# RP2350B_DEV_Template.net
KiCad netlist of a schematic drawn in EAGLE
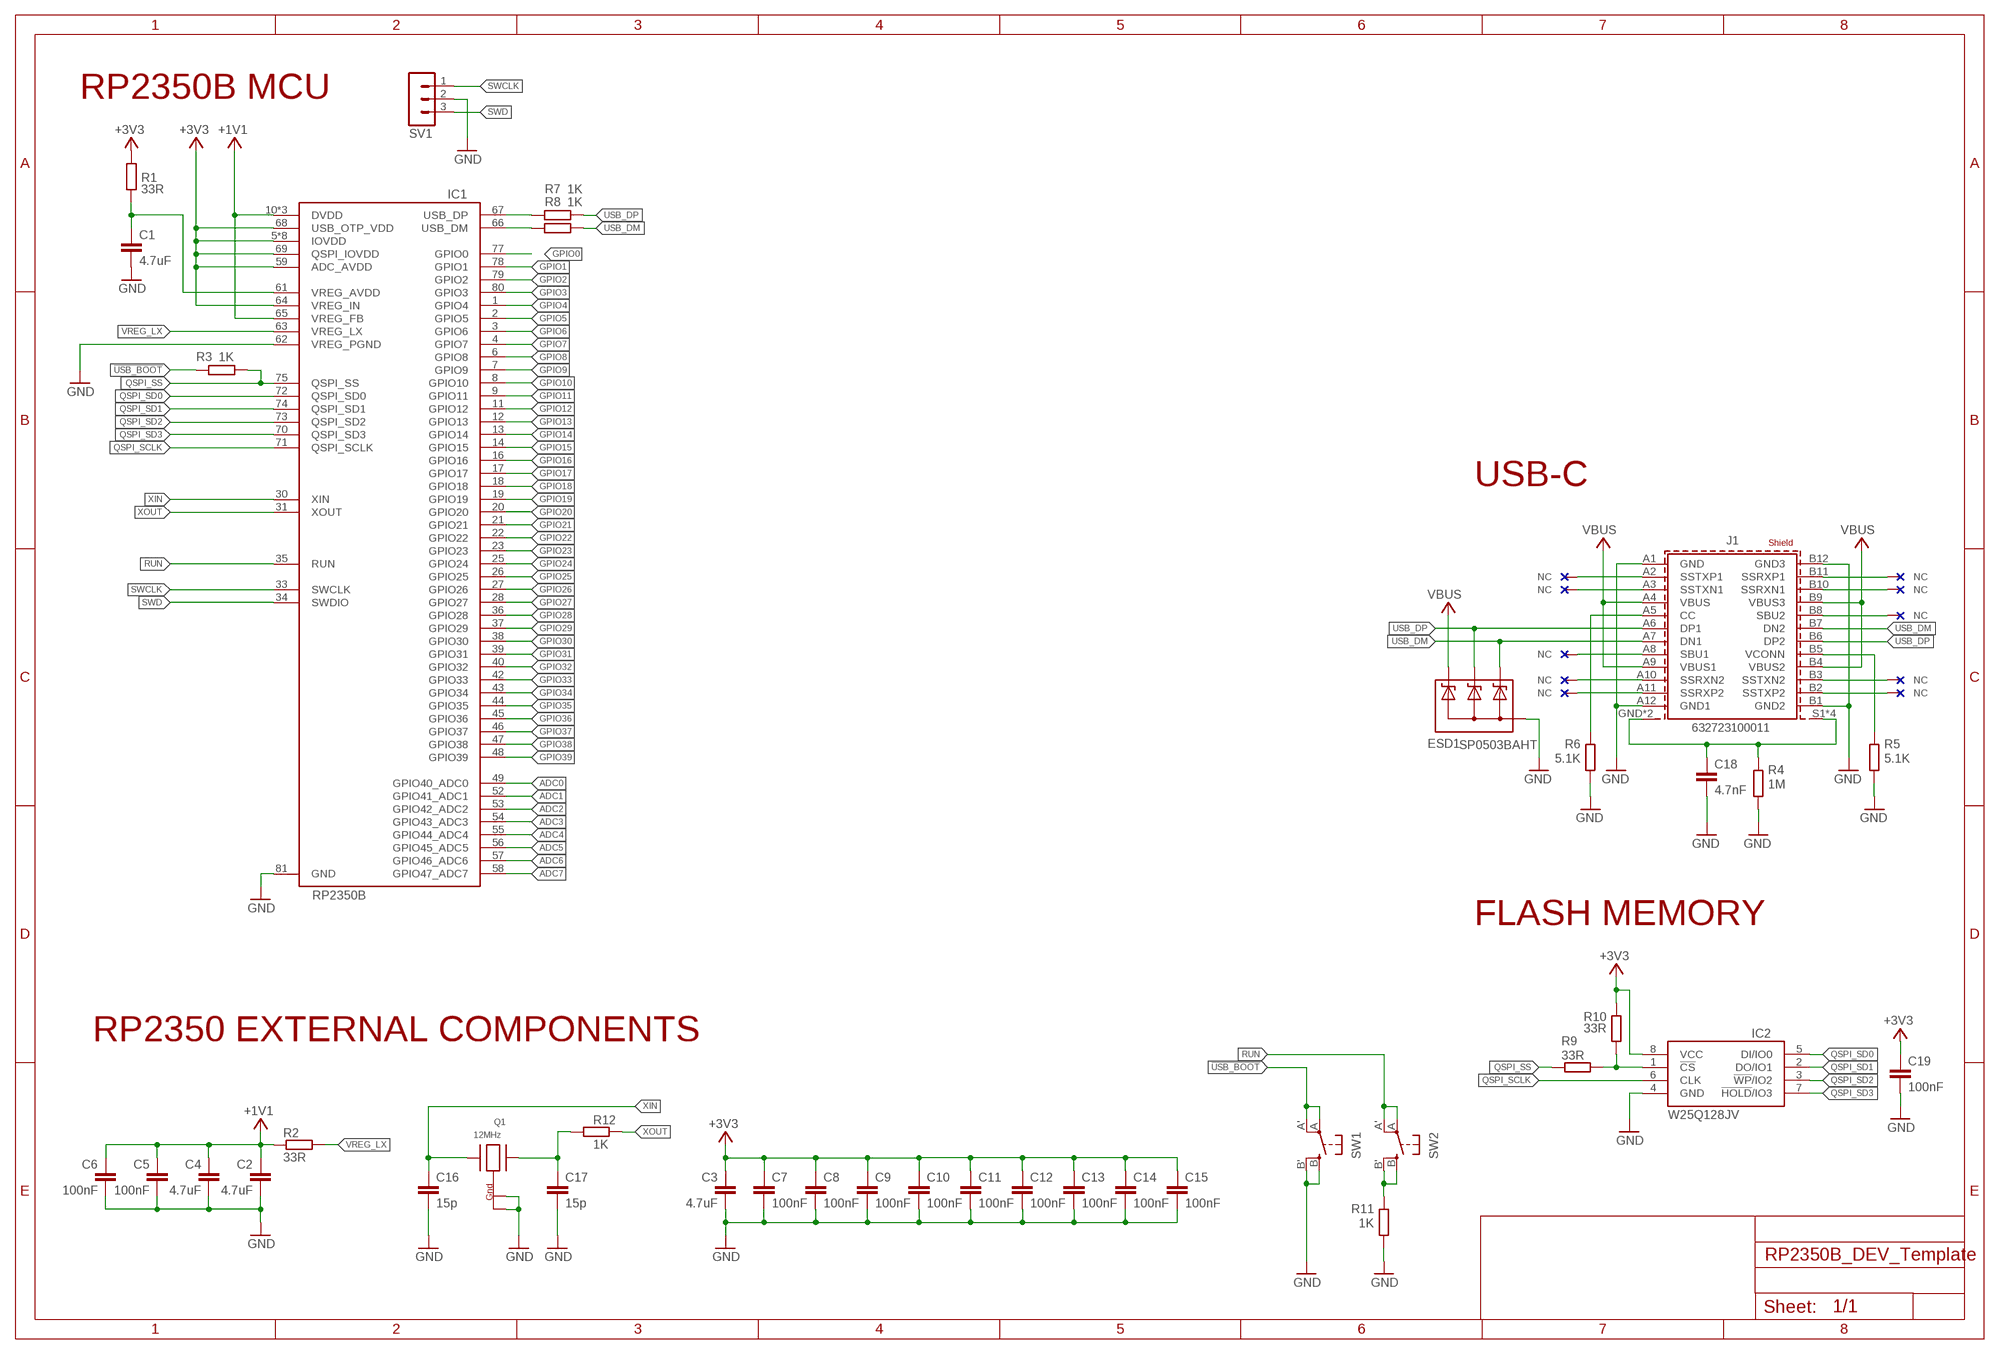
[diagram p0: schematic, sheet 1]

(export (version "E")
  (design (tool "Eeschema 10.0.6"))
  (components
    (comp (ref "C1")
      (value "4.7uF")
      (footprint "eagle-import:C0402K")
      (libsource (lib "eagle-import") (part "C-EUC0402K"))
    )
    (comp (ref "C2")
      (value "4.7uF")
      (footprint "eagle-import:C0402K")
      (libsource (lib "eagle-import") (part "C-EUC0402K"))
    )
    (comp (ref "C3")
      (value "4.7uF")
      (footprint "eagle-import:C0402K")
      (libsource (lib "eagle-import") (part "C-EUC0402K"))
    )
    (comp (ref "C4")
      (value "4.7uF")
      (footprint "eagle-import:C0402K")
      (libsource (lib "eagle-import") (part "C-EUC0402K"))
    )
    (comp (ref "C5")
      (value "100nF")
      (footprint "eagle-import:C0402K")
      (libsource (lib "eagle-import") (part "C-EUC0402K"))
    )
    (comp (ref "C6")
      (value "100nF")
      (footprint "eagle-import:C0402K")
      (libsource (lib "eagle-import") (part "C-EUC0402K"))
    )
    (comp (ref "C7")
      (value "100nF")
      (footprint "eagle-import:C0402K")
      (libsource (lib "eagle-import") (part "C-EUC0402K"))
    )
    (comp (ref "C8")
      (value "100nF")
      (footprint "eagle-import:C0402K")
      (libsource (lib "eagle-import") (part "C-EUC0402K"))
    )
    (comp (ref "C9")
      (value "100nF")
      (footprint "eagle-import:C0402K")
      (libsource (lib "eagle-import") (part "C-EUC0402K"))
    )
    (comp (ref "C10")
      (value "100nF")
      (footprint "eagle-import:C0402K")
      (libsource (lib "eagle-import") (part "C-EUC0402K"))
    )
    (comp (ref "C11")
      (value "100nF")
      (footprint "eagle-import:C0402K")
      (libsource (lib "eagle-import") (part "C-EUC0402K"))
    )
    (comp (ref "C12")
      (value "100nF")
      (footprint "eagle-import:C0402K")
      (libsource (lib "eagle-import") (part "C-EUC0402K"))
    )
    (comp (ref "C13")
      (value "100nF")
      (footprint "eagle-import:C0402K")
      (libsource (lib "eagle-import") (part "C-EUC0402K"))
    )
    (comp (ref "C14")
      (value "100nF")
      (footprint "eagle-import:C0402K")
      (libsource (lib "eagle-import") (part "C-EUC0402K"))
    )
    (comp (ref "C15")
      (value "100nF")
      (footprint "eagle-import:C0402K")
      (libsource (lib "eagle-import") (part "C-EUC0402K"))
    )
    (comp (ref "C16")
      (value "15p")
      (footprint "eagle-import:C0402K")
      (libsource (lib "eagle-import") (part "C-EUC0402K"))
    )
    (comp (ref "C17")
      (value "15p")
      (footprint "eagle-import:C0402K")
      (libsource (lib "eagle-import") (part "C-EUC0402K"))
    )
    (comp (ref "C18")
      (value "4.7nF")
      (footprint "eagle-import:C0402K")
      (libsource (lib "eagle-import") (part "C-EUC0402K"))
    )
    (comp (ref "C19")
      (value "100nF")
      (footprint "eagle-import:C0402K")
      (libsource (lib "eagle-import") (part "C-EUC0402K"))
    )
    (comp (ref "ESD1")
      (value "SP0503BAHT")
      (footprint "eagle-import:SOT143")
      (libsource (lib "eagle-import") (part "SP0503BAHT"))
    )
    (comp (ref "IC1")
      (value "RP2350BB")
      (footprint "eagle-import:QFN40P1000X1000X85-81T340N")
      (libsource (lib "eagle-import") (part "RP2350BB"))
    )
    (comp (ref "IC2")
      (value "W25Q128JVP")
      (footprint "eagle-import:SON127P600X500X75-8N")
      (libsource (lib "eagle-import") (part "W25Q128JVP"))
    )
    (comp (ref "J1")
      (value "632723100011")
      (footprint "eagle-import:632723100011")
      (libsource (lib "eagle-import") (part "632723100011"))
    )
    (comp (ref "Q1")
      (value "12MHz")
      (footprint "eagle-import:NX3225")
      (libsource (lib "eagle-import") (part "XTAL-4-3225"))
    )
    (comp (ref "R1")
      (value "33R")
      (footprint "eagle-import:R0402")
      (libsource (lib "eagle-import") (part "R-EU_R0402"))
    )
    (comp (ref "R2")
      (value "33R")
      (footprint "eagle-import:R0402")
      (libsource (lib "eagle-import") (part "R-EU_R0402"))
    )
    (comp (ref "R3")
      (value "1K")
      (footprint "eagle-import:R0402")
      (libsource (lib "eagle-import") (part "R-EU_R0402"))
    )
    (comp (ref "R4")
      (value "1M")
      (footprint "eagle-import:R0402")
      (libsource (lib "eagle-import") (part "R-EU_R0402"))
    )
    (comp (ref "R5")
      (value "5.1K")
      (footprint "eagle-import:R0402")
      (libsource (lib "eagle-import") (part "R-EU_R0402"))
    )
    (comp (ref "R6")
      (value "5.1K")
      (footprint "eagle-import:R0402")
      (libsource (lib "eagle-import") (part "R-EU_R0402"))
    )
    (comp (ref "R7")
      (value "1K")
      (footprint "eagle-import:R0402")
      (libsource (lib "eagle-import") (part "R-EU_R0402"))
    )
    (comp (ref "R8")
      (value "1K")
      (footprint "eagle-import:R0402")
      (libsource (lib "eagle-import") (part "R-EU_R0402"))
    )
    (comp (ref "R9")
      (value "33R")
      (footprint "eagle-import:R0402")
      (libsource (lib "eagle-import") (part "R-EU_R0402"))
    )
    (comp (ref "R10")
      (value "33R")
      (footprint "eagle-import:R0402")
      (libsource (lib "eagle-import") (part "R-EU_R0402"))
    )
    (comp (ref "R11")
      (value "1K")
      (footprint "eagle-import:R0402")
      (libsource (lib "eagle-import") (part "R-EU_R0402"))
    )
    (comp (ref "R12")
      (value "1K")
      (footprint "eagle-import:R0402")
      (libsource (lib "eagle-import") (part "R-EU_R0402"))
    )
    (comp (ref "SV1")
      (value "MA03-1")
      (footprint "eagle-import:MA03-1")
      (libsource (lib "eagle-import") (part "MA03-1"))
    )
    (comp (ref "SW1")
      (value "SPST_TACT-EVQQ2")
      (footprint "eagle-import:EVQ-Q2")
      (libsource (lib "eagle-import") (part "SPST_TACT-EVQQ2"))
    )
    (comp (ref "SW2")
      (value "SPST_TACT-EVQQ2")
      (footprint "eagle-import:EVQ-Q2")
      (libsource (lib "eagle-import") (part "SPST_TACT-EVQQ2"))
    )
  )
  (nets
    (net (code "1") (name "+1V1") (class "Default")
      (node (ref "C2") (pin "1") (pinfunction "1_1") (pintype "passive"))
      (node (ref "C4") (pin "1") (pinfunction "1_1") (pintype "passive"))
      (node (ref "C5") (pin "1") (pinfunction "1_1") (pintype "passive"))
      (node (ref "C6") (pin "1") (pinfunction "1_1") (pintype "passive"))
      (node (ref "IC1") (pin "10") (pinfunction "DVDD_10") (pintype "power_in"))
      (node (ref "IC1") (pin "32") (pinfunction "DVDD_32") (pintype "power_in"))
      (node (ref "IC1") (pin "51") (pinfunction "DVDD_51") (pintype "power_in"))
      (node (ref "IC1") (pin "65") (pinfunction "VREG_FB_65") (pintype "power_in"))
      (node (ref "R2") (pin "2") (pinfunction "2_2") (pintype "passive"))
    )
    (net (code "2") (name "+3V3") (class "Default")
      (node (ref "C10") (pin "1") (pinfunction "1_1") (pintype "passive"))
      (node (ref "C11") (pin "1") (pinfunction "1_1") (pintype "passive"))
      (node (ref "C12") (pin "1") (pinfunction "1_1") (pintype "passive"))
      (node (ref "C13") (pin "1") (pinfunction "1_1") (pintype "passive"))
      (node (ref "C14") (pin "1") (pinfunction "1_1") (pintype "passive"))
      (node (ref "C15") (pin "1") (pinfunction "1_1") (pintype "passive"))
      (node (ref "C19") (pin "1") (pinfunction "1_1") (pintype "passive"))
      (node (ref "C3") (pin "1") (pinfunction "1_1") (pintype "passive"))
      (node (ref "C7") (pin "1") (pinfunction "1_1") (pintype "passive"))
      (node (ref "C8") (pin "1") (pinfunction "1_1") (pintype "passive"))
      (node (ref "C9") (pin "1") (pinfunction "1_1") (pintype "passive"))
      (node (ref "IC1") (pin "15") (pinfunction "IOVDD_15") (pintype "power_in"))
      (node (ref "IC1") (pin "24") (pinfunction "IOVDD_24") (pintype "power_in"))
      (node (ref "IC1") (pin "29") (pinfunction "IOVDD_29") (pintype "power_in"))
      (node (ref "IC1") (pin "41") (pinfunction "IOVDD_41") (pintype "power_in"))
      (node (ref "IC1") (pin "5") (pinfunction "IOVDD_5") (pintype "power_in"))
      (node (ref "IC1") (pin "50") (pinfunction "IOVDD_50") (pintype "power_in"))
      (node (ref "IC1") (pin "59") (pinfunction "ADC_AVDD_59") (pintype "power_in"))
      (node (ref "IC1") (pin "60") (pinfunction "IOVDD_60") (pintype "power_in"))
      (node (ref "IC1") (pin "64") (pinfunction "VREG_IN_64") (pintype "power_in"))
      (node (ref "IC1") (pin "68") (pinfunction "USB_OTP_VDD_68") (pintype "bidirectional"))
      (node (ref "IC1") (pin "69") (pinfunction "QSPI_IOVDD_69") (pintype "power_in"))
      (node (ref "IC1") (pin "76") (pinfunction "IOVDD_76") (pintype "power_in"))
      (node (ref "IC2") (pin "8") (pinfunction "VCC_8") (pintype "power_in"))
      (node (ref "R1") (pin "1") (pinfunction "1_1") (pintype "passive"))
      (node (ref "R10") (pin "1") (pinfunction "1_1") (pintype "passive"))
    )
    (net (code "3") (name "/~{USB_BOOT}") (class "Default")
      (node (ref "R3") (pin "1") (pinfunction "1_1") (pintype "passive"))
      (node (ref "SW1") (pin "A") (pinfunction "P_A") (pintype "passive"))
      (node (ref "SW1") (pin "A'") (pinfunction "P1_A'") (pintype "passive"))
    )
    (net (code "4") (name "ADC0") (class "Default")
      (node (ref "IC1") (pin "49") (pinfunction "GPIO40_ADC0_49") (pintype "bidirectional"))
    )
    (net (code "5") (name "ADC1") (class "Default")
      (node (ref "IC1") (pin "52") (pinfunction "GPIO41_ADC1_52") (pintype "bidirectional"))
    )
    (net (code "6") (name "ADC2") (class "Default")
      (node (ref "IC1") (pin "53") (pinfunction "GPIO42_ADC2_53") (pintype "bidirectional"))
    )
    (net (code "7") (name "ADC3") (class "Default")
      (node (ref "IC1") (pin "54") (pinfunction "GPIO43_ADC3_54") (pintype "bidirectional"))
    )
    (net (code "8") (name "ADC4") (class "Default")
      (node (ref "IC1") (pin "55") (pinfunction "GPIO44_ADC4_55") (pintype "bidirectional"))
    )
    (net (code "9") (name "ADC5") (class "Default")
      (node (ref "IC1") (pin "56") (pinfunction "GPIO45_ADC5_56") (pintype "bidirectional"))
    )
    (net (code "10") (name "ADC6") (class "Default")
      (node (ref "IC1") (pin "57") (pinfunction "GPIO46_ADC6_57") (pintype "bidirectional"))
    )
    (net (code "11") (name "ADC7") (class "Default")
      (node (ref "IC1") (pin "58") (pinfunction "GPIO47_ADC7_58") (pintype "bidirectional"))
    )
    (net (code "12") (name "GND") (class "Default")
      (node (ref "C1") (pin "2") (pinfunction "2_2") (pintype "passive"))
      (node (ref "C10") (pin "2") (pinfunction "2_2") (pintype "passive"))
      (node (ref "C11") (pin "2") (pinfunction "2_2") (pintype "passive"))
      (node (ref "C12") (pin "2") (pinfunction "2_2") (pintype "passive"))
      (node (ref "C13") (pin "2") (pinfunction "2_2") (pintype "passive"))
      (node (ref "C14") (pin "2") (pinfunction "2_2") (pintype "passive"))
      (node (ref "C15") (pin "2") (pinfunction "2_2") (pintype "passive"))
      (node (ref "C16") (pin "2") (pinfunction "2_2") (pintype "passive"))
      (node (ref "C17") (pin "2") (pinfunction "2_2") (pintype "passive"))
      (node (ref "C18") (pin "2") (pinfunction "2_2") (pintype "passive"))
      (node (ref "C19") (pin "2") (pinfunction "2_2") (pintype "passive"))
      (node (ref "C2") (pin "2") (pinfunction "2_2") (pintype "passive"))
      (node (ref "C3") (pin "2") (pinfunction "2_2") (pintype "passive"))
      (node (ref "C4") (pin "2") (pinfunction "2_2") (pintype "passive"))
      (node (ref "C5") (pin "2") (pinfunction "2_2") (pintype "passive"))
      (node (ref "C6") (pin "2") (pinfunction "2_2") (pintype "passive"))
      (node (ref "C7") (pin "2") (pinfunction "2_2") (pintype "passive"))
      (node (ref "C8") (pin "2") (pinfunction "2_2") (pintype "passive"))
      (node (ref "C9") (pin "2") (pinfunction "2_2") (pintype "passive"))
      (node (ref "ESD1") (pin "1") (pinfunction "A_1") (pintype "bidirectional"))
      (node (ref "IC1") (pin "62") (pinfunction "VREG_PGND_62") (pintype "power_in"))
      (node (ref "IC1") (pin "81") (pinfunction "GND_81") (pintype "power_in"))
      (node (ref "IC2") (pin "4") (pinfunction "GND_4") (pintype "power_in"))
      (node (ref "J1") (pin "A1") (pinfunction "GND_A1") (pintype "passive"))
      (node (ref "J1") (pin "A12") (pinfunction "GND1_A12") (pintype "passive"))
      (node (ref "J1") (pin "B1") (pinfunction "GND2_B1") (pintype "passive"))
      (node (ref "J1") (pin "B12") (pinfunction "GND3_B12") (pintype "passive"))
      (node (ref "Q1") (pin "2") (pinfunction "G2_2") (pintype "power_in"))
      (node (ref "Q1") (pin "4") (pinfunction "G1_4") (pintype "power_in"))
      (node (ref "R11") (pin "1") (pinfunction "1_1") (pintype "passive"))
      (node (ref "R4") (pin "1") (pinfunction "1_1") (pintype "passive"))
      (node (ref "R5") (pin "1") (pinfunction "1_1") (pintype "passive"))
      (node (ref "R6") (pin "1") (pinfunction "1_1") (pintype "passive"))
      (node (ref "SV1") (pin "2") (pinfunction "2_2") (pintype "passive"))
      (node (ref "SW1") (pin "B") (pinfunction "S_B") (pintype "passive"))
      (node (ref "SW1") (pin "B'") (pinfunction "S1_B'") (pintype "passive"))
    )
    (net (code "13") (name "GPIO0") (class "Default")
      (node (ref "IC1") (pin "77") (pinfunction "GPIO0_77") (pintype "bidirectional"))
    )
    (net (code "14") (name "GPIO1") (class "Default")
      (node (ref "IC1") (pin "78") (pinfunction "GPIO1_78") (pintype "bidirectional"))
    )
    (net (code "15") (name "GPIO2") (class "Default")
      (node (ref "IC1") (pin "79") (pinfunction "GPIO2_79") (pintype "bidirectional"))
    )
    (net (code "16") (name "GPIO3") (class "Default")
      (node (ref "IC1") (pin "80") (pinfunction "GPIO3_80") (pintype "bidirectional"))
    )
    (net (code "17") (name "GPIO4") (class "Default")
      (node (ref "IC1") (pin "1") (pinfunction "GPIO4_1") (pintype "bidirectional"))
    )
    (net (code "18") (name "GPIO5") (class "Default")
      (node (ref "IC1") (pin "2") (pinfunction "GPIO5_2") (pintype "bidirectional"))
    )
    (net (code "19") (name "GPIO6") (class "Default")
      (node (ref "IC1") (pin "3") (pinfunction "GPIO6_3") (pintype "bidirectional"))
    )
    (net (code "20") (name "GPIO7") (class "Default")
      (node (ref "IC1") (pin "4") (pinfunction "GPIO7_4") (pintype "bidirectional"))
    )
    (net (code "21") (name "GPIO8") (class "Default")
      (node (ref "IC1") (pin "6") (pinfunction "GPIO8_6") (pintype "bidirectional"))
    )
    (net (code "22") (name "GPIO9") (class "Default")
      (node (ref "IC1") (pin "7") (pinfunction "GPIO9_7") (pintype "bidirectional"))
    )
    (net (code "23") (name "GPIO10") (class "Default")
      (node (ref "IC1") (pin "8") (pinfunction "GPIO10_8") (pintype "bidirectional"))
    )
    (net (code "24") (name "GPIO11") (class "Default")
      (node (ref "IC1") (pin "9") (pinfunction "GPIO11_9") (pintype "bidirectional"))
    )
    (net (code "25") (name "GPIO12") (class "Default")
      (node (ref "IC1") (pin "11") (pinfunction "GPIO12_11") (pintype "bidirectional"))
    )
    (net (code "26") (name "GPIO13") (class "Default")
      (node (ref "IC1") (pin "12") (pinfunction "GPIO13_12") (pintype "bidirectional"))
    )
    (net (code "27") (name "GPIO14") (class "Default")
      (node (ref "IC1") (pin "13") (pinfunction "GPIO14_13") (pintype "bidirectional"))
    )
    (net (code "28") (name "GPIO15") (class "Default")
      (node (ref "IC1") (pin "14") (pinfunction "GPIO15_14") (pintype "bidirectional"))
    )
    (net (code "29") (name "GPIO16") (class "Default")
      (node (ref "IC1") (pin "16") (pinfunction "GPIO16_16") (pintype "bidirectional"))
    )
    (net (code "30") (name "GPIO17") (class "Default")
      (node (ref "IC1") (pin "17") (pinfunction "GPIO17_17") (pintype "bidirectional"))
    )
    (net (code "31") (name "GPIO18") (class "Default")
      (node (ref "IC1") (pin "18") (pinfunction "GPIO18_18") (pintype "bidirectional"))
    )
    (net (code "32") (name "GPIO19") (class "Default")
      (node (ref "IC1") (pin "19") (pinfunction "GPIO19_19") (pintype "bidirectional"))
    )
    (net (code "33") (name "GPIO20") (class "Default")
      (node (ref "IC1") (pin "20") (pinfunction "GPIO20_20") (pintype "bidirectional"))
    )
    (net (code "34") (name "GPIO21") (class "Default")
      (node (ref "IC1") (pin "21") (pinfunction "GPIO21_21") (pintype "bidirectional"))
    )
    (net (code "35") (name "GPIO22") (class "Default")
      (node (ref "IC1") (pin "22") (pinfunction "GPIO22_22") (pintype "bidirectional"))
    )
    (net (code "36") (name "GPIO23") (class "Default")
      (node (ref "IC1") (pin "23") (pinfunction "GPIO23_23") (pintype "bidirectional"))
    )
    (net (code "37") (name "GPIO24") (class "Default")
      (node (ref "IC1") (pin "25") (pinfunction "GPIO24_25") (pintype "bidirectional"))
    )
    (net (code "38") (name "GPIO25") (class "Default")
      (node (ref "IC1") (pin "26") (pinfunction "GPIO25_26") (pintype "bidirectional"))
    )
    (net (code "39") (name "GPIO26") (class "Default")
      (node (ref "IC1") (pin "27") (pinfunction "GPIO26_27") (pintype "bidirectional"))
    )
    (net (code "40") (name "GPIO27") (class "Default")
      (node (ref "IC1") (pin "28") (pinfunction "GPIO27_28") (pintype "bidirectional"))
    )
    (net (code "41") (name "GPIO28") (class "Default")
      (node (ref "IC1") (pin "36") (pinfunction "GPIO28_36") (pintype "bidirectional"))
    )
    (net (code "42") (name "GPIO29") (class "Default")
      (node (ref "IC1") (pin "37") (pinfunction "GPIO29_37") (pintype "bidirectional"))
    )
    (net (code "43") (name "GPIO30") (class "Default")
      (node (ref "IC1") (pin "38") (pinfunction "GPIO30_38") (pintype "bidirectional"))
    )
    (net (code "44") (name "GPIO31") (class "Default")
      (node (ref "IC1") (pin "39") (pinfunction "GPIO31_39") (pintype "bidirectional"))
    )
    (net (code "45") (name "GPIO32") (class "Default")
      (node (ref "IC1") (pin "40") (pinfunction "GPIO32_40") (pintype "bidirectional"))
    )
    (net (code "46") (name "GPIO33") (class "Default")
      (node (ref "IC1") (pin "42") (pinfunction "GPIO33_42") (pintype "bidirectional"))
    )
    (net (code "47") (name "GPIO34") (class "Default")
      (node (ref "IC1") (pin "43") (pinfunction "GPIO34_43") (pintype "bidirectional"))
    )
    (net (code "48") (name "GPIO35") (class "Default")
      (node (ref "IC1") (pin "44") (pinfunction "GPIO35_44") (pintype "bidirectional"))
    )
    (net (code "49") (name "GPIO36") (class "Default")
      (node (ref "IC1") (pin "45") (pinfunction "GPIO36_45") (pintype "bidirectional"))
    )
    (net (code "50") (name "GPIO37") (class "Default")
      (node (ref "IC1") (pin "46") (pinfunction "GPIO37_46") (pintype "bidirectional"))
    )
    (net (code "51") (name "GPIO38") (class "Default")
      (node (ref "IC1") (pin "47") (pinfunction "GPIO38_47") (pintype "bidirectional"))
    )
    (net (code "52") (name "GPIO39") (class "Default")
      (node (ref "IC1") (pin "48") (pinfunction "GPIO39_48") (pintype "bidirectional"))
    )
    (net (code "53") (name "Net-(C18-Pad1)") (class "Default")
      (node (ref "C18") (pin "1") (pinfunction "1_1") (pintype "passive"))
      (node (ref "J1") (pin "GND") (pinfunction "SHIELD_GND") (pintype "passive"))
      (node (ref "J1") (pin "GND1") (pinfunction "SHIELD_GND1") (pintype "passive"))
      (node (ref "J1") (pin "S1") (pinfunction "SHIELD1_S1") (pintype "passive"))
      (node (ref "J1") (pin "S2") (pinfunction "SHIELD1_S2") (pintype "passive"))
      (node (ref "J1") (pin "S3") (pinfunction "SHIELD1_S3") (pintype "passive"))
      (node (ref "J1") (pin "S4") (pinfunction "SHIELD1_S4") (pintype "passive"))
      (node (ref "R4") (pin "2") (pinfunction "2_2") (pintype "passive"))
    )
    (net (code "54") (name "Net-(IC1-USB_DM)") (class "Default")
      (node (ref "IC1") (pin "66") (pinfunction "USB_DM_66") (pintype "bidirectional"))
      (node (ref "R8") (pin "1") (pinfunction "1_1") (pintype "passive"))
    )
    (net (code "55") (name "Net-(IC1-USB_DP)") (class "Default")
      (node (ref "IC1") (pin "67") (pinfunction "USB_DP_67") (pintype "bidirectional"))
      (node (ref "R7") (pin "1") (pinfunction "1_1") (pintype "passive"))
    )
    (net (code "56") (name "Net-(IC1-VREG_AVDD)") (class "Default")
      (node (ref "C1") (pin "1") (pinfunction "1_1") (pintype "passive"))
      (node (ref "IC1") (pin "61") (pinfunction "VREG_AVDD_61") (pintype "power_in"))
      (node (ref "R1") (pin "2") (pinfunction "2_2") (pintype "passive"))
    )
    (net (code "57") (name "Net-(IC2-~{CS})") (class "Default")
      (node (ref "IC2") (pin "1") (pinfunction "~{CS}_1") (pintype "bidirectional"))
      (node (ref "R10") (pin "2") (pinfunction "2_2") (pintype "passive"))
      (node (ref "R9") (pin "2") (pinfunction "2_2") (pintype "passive"))
    )
    (net (code "58") (name "Net-(J1-CC)") (class "Default")
      (node (ref "J1") (pin "A5") (pinfunction "CC_A5") (pintype "passive"))
      (node (ref "R6") (pin "2") (pinfunction "2_2") (pintype "passive"))
    )
    (net (code "59") (name "Net-(J1-VCONN)") (class "Default")
      (node (ref "J1") (pin "B5") (pinfunction "VCONN_B5") (pintype "passive"))
      (node (ref "R5") (pin "2") (pinfunction "2_2") (pintype "passive"))
    )
    (net (code "60") (name "Net-(Q1-X1)") (class "Default")
      (node (ref "C17") (pin "1") (pinfunction "1_1") (pintype "passive"))
      (node (ref "Q1") (pin "1") (pinfunction "X1_1") (pintype "bidirectional"))
      (node (ref "R12") (pin "1") (pinfunction "1_1") (pintype "passive"))
    )
    (net (code "61") (name "Net-(SW2-S)") (class "Default")
      (node (ref "R11") (pin "2") (pinfunction "2_2") (pintype "passive"))
      (node (ref "SW2") (pin "B") (pinfunction "S_B") (pintype "passive"))
      (node (ref "SW2") (pin "B'") (pinfunction "S1_B'") (pintype "passive"))
    )
    (net (code "62") (name "QSPI_SCLK") (class "Default")
      (node (ref "IC1") (pin "71") (pinfunction "QSPI_SCLK_71") (pintype "bidirectional"))
      (node (ref "IC2") (pin "6") (pinfunction "CLK_6") (pintype "bidirectional"))
    )
    (net (code "63") (name "QSPI_SD0") (class "Default")
      (node (ref "IC1") (pin "72") (pinfunction "QSPI_SD0_72") (pintype "bidirectional"))
      (node (ref "IC2") (pin "5") (pinfunction "DI/IO0_5") (pintype "bidirectional"))
    )
    (net (code "64") (name "QSPI_SD1") (class "Default")
      (node (ref "IC1") (pin "74") (pinfunction "QSPI_SD1_74") (pintype "bidirectional"))
      (node (ref "IC2") (pin "2") (pinfunction "DO/IO1_2") (pintype "bidirectional"))
    )
    (net (code "65") (name "QSPI_SD2") (class "Default")
      (node (ref "IC1") (pin "73") (pinfunction "QSPI_SD2_73") (pintype "bidirectional"))
      (node (ref "IC2") (pin "3") (pinfunction "~{WP}/IO2_3") (pintype "bidirectional"))
    )
    (net (code "66") (name "QSPI_SD3") (class "Default")
      (node (ref "IC1") (pin "70") (pinfunction "QSPI_SD3_70") (pintype "bidirectional"))
      (node (ref "IC2") (pin "7") (pinfunction "~{HOLD}/IO3_7") (pintype "bidirectional"))
    )
    (net (code "67") (name "QSPI_SS") (class "Default")
      (node (ref "IC1") (pin "75") (pinfunction "QSPI_SS_75") (pintype "bidirectional"))
      (node (ref "R3") (pin "2") (pinfunction "2_2") (pintype "passive"))
      (node (ref "R9") (pin "1") (pinfunction "1_1") (pintype "passive"))
    )
    (net (code "68") (name "RUN") (class "Default")
      (node (ref "IC1") (pin "35") (pinfunction "RUN_35") (pintype "bidirectional"))
      (node (ref "SW2") (pin "A") (pinfunction "P_A") (pintype "passive"))
      (node (ref "SW2") (pin "A'") (pinfunction "P1_A'") (pintype "passive"))
    )
    (net (code "69") (name "SWCLK") (class "Default")
      (node (ref "IC1") (pin "33") (pinfunction "SWCLK_33") (pintype "bidirectional"))
      (node (ref "SV1") (pin "1") (pinfunction "1_1") (pintype "passive"))
    )
    (net (code "70") (name "SWD") (class "Default")
      (node (ref "IC1") (pin "34") (pinfunction "SWDIO_34") (pintype "bidirectional"))
      (node (ref "SV1") (pin "3") (pinfunction "3_3") (pintype "passive"))
    )
    (net (code "71") (name "USB_DM") (class "Default")
      (node (ref "ESD1") (pin "2") (pinfunction "C1_2") (pintype "bidirectional"))
      (node (ref "J1") (pin "A7") (pinfunction "DN1_A7") (pintype "passive"))
      (node (ref "J1") (pin "B7") (pinfunction "DN2_B7") (pintype "passive"))
      (node (ref "R8") (pin "2") (pinfunction "2_2") (pintype "passive"))
    )
    (net (code "72") (name "USB_DP") (class "Default")
      (node (ref "ESD1") (pin "3") (pinfunction "C2_3") (pintype "bidirectional"))
      (node (ref "J1") (pin "A6") (pinfunction "DP1_A6") (pintype "passive"))
      (node (ref "J1") (pin "B6") (pinfunction "DP2_B6") (pintype "passive"))
      (node (ref "R7") (pin "2") (pinfunction "2_2") (pintype "passive"))
    )
    (net (code "73") (name "VBUS") (class "Default")
      (node (ref "ESD1") (pin "4") (pinfunction "C3_4") (pintype "bidirectional"))
      (node (ref "J1") (pin "A4") (pinfunction "VBUS_A4") (pintype "passive"))
      (node (ref "J1") (pin "A9") (pinfunction "VBUS1_A9") (pintype "passive"))
      (node (ref "J1") (pin "B4") (pinfunction "VBUS2_B4") (pintype "passive"))
      (node (ref "J1") (pin "B9") (pinfunction "VBUS3_B9") (pintype "passive"))
    )
    (net (code "74") (name "VREG_LX") (class "Default")
      (node (ref "IC1") (pin "63") (pinfunction "VREG_LX_63") (pintype "power_in"))
      (node (ref "R2") (pin "1") (pinfunction "1_1") (pintype "passive"))
    )
    (net (code "75") (name "XIN") (class "Default")
      (node (ref "C16") (pin "1") (pinfunction "1_1") (pintype "passive"))
      (node (ref "IC1") (pin "30") (pinfunction "XIN_30") (pintype "input"))
      (node (ref "Q1") (pin "3") (pinfunction "X2_3") (pintype "bidirectional"))
    )
    (net (code "76") (name "XOUT") (class "Default")
      (node (ref "IC1") (pin "31") (pinfunction "XOUT_31") (pintype "output"))
      (node (ref "R12") (pin "2") (pinfunction "2_2") (pintype "passive"))
    )
    (net (code "77") (name "unconnected-(J1-SBU1-PadA8)") (class "Default")
      (node (ref "J1") (pin "A8") (pinfunction "SBU1_A8") (pintype "passive"))
    )
    (net (code "78") (name "unconnected-(J1-SBU2-PadB8)") (class "Default")
      (node (ref "J1") (pin "B8") (pinfunction "SBU2_B8") (pintype "passive"))
    )
    (net (code "79") (name "unconnected-(J1-SSRXN1-PadB10)") (class "Default")
      (node (ref "J1") (pin "B10") (pinfunction "SSRXN1_B10") (pintype "passive"))
    )
    (net (code "80") (name "unconnected-(J1-SSRXN2-PadA10)") (class "Default")
      (node (ref "J1") (pin "A10") (pinfunction "SSRXN2_A10") (pintype "passive"))
    )
    (net (code "81") (name "unconnected-(J1-SSRXP1-PadB11)") (class "Default")
      (node (ref "J1") (pin "B11") (pinfunction "SSRXP1_B11") (pintype "passive"))
    )
    (net (code "82") (name "unconnected-(J1-SSRXP2-PadA11)") (class "Default")
      (node (ref "J1") (pin "A11") (pinfunction "SSRXP2_A11") (pintype "passive"))
    )
    (net (code "83") (name "unconnected-(J1-SSTXN1-PadA3)") (class "Default")
      (node (ref "J1") (pin "A3") (pinfunction "SSTXN1_A3") (pintype "passive"))
    )
    (net (code "84") (name "unconnected-(J1-SSTXN2-PadB3)") (class "Default")
      (node (ref "J1") (pin "B3") (pinfunction "SSTXN2_B3") (pintype "passive"))
    )
    (net (code "85") (name "unconnected-(J1-SSTXP1-PadA2)") (class "Default")
      (node (ref "J1") (pin "A2") (pinfunction "SSTXP1_A2") (pintype "passive"))
    )
    (net (code "86") (name "unconnected-(J1-SSTXP2-PadB2)") (class "Default")
      (node (ref "J1") (pin "B2") (pinfunction "SSTXP2_B2") (pintype "passive"))
    )
  )
)
